# 10_BOOT.net
KiCad netlist of a schematic drawn in Altium Designer
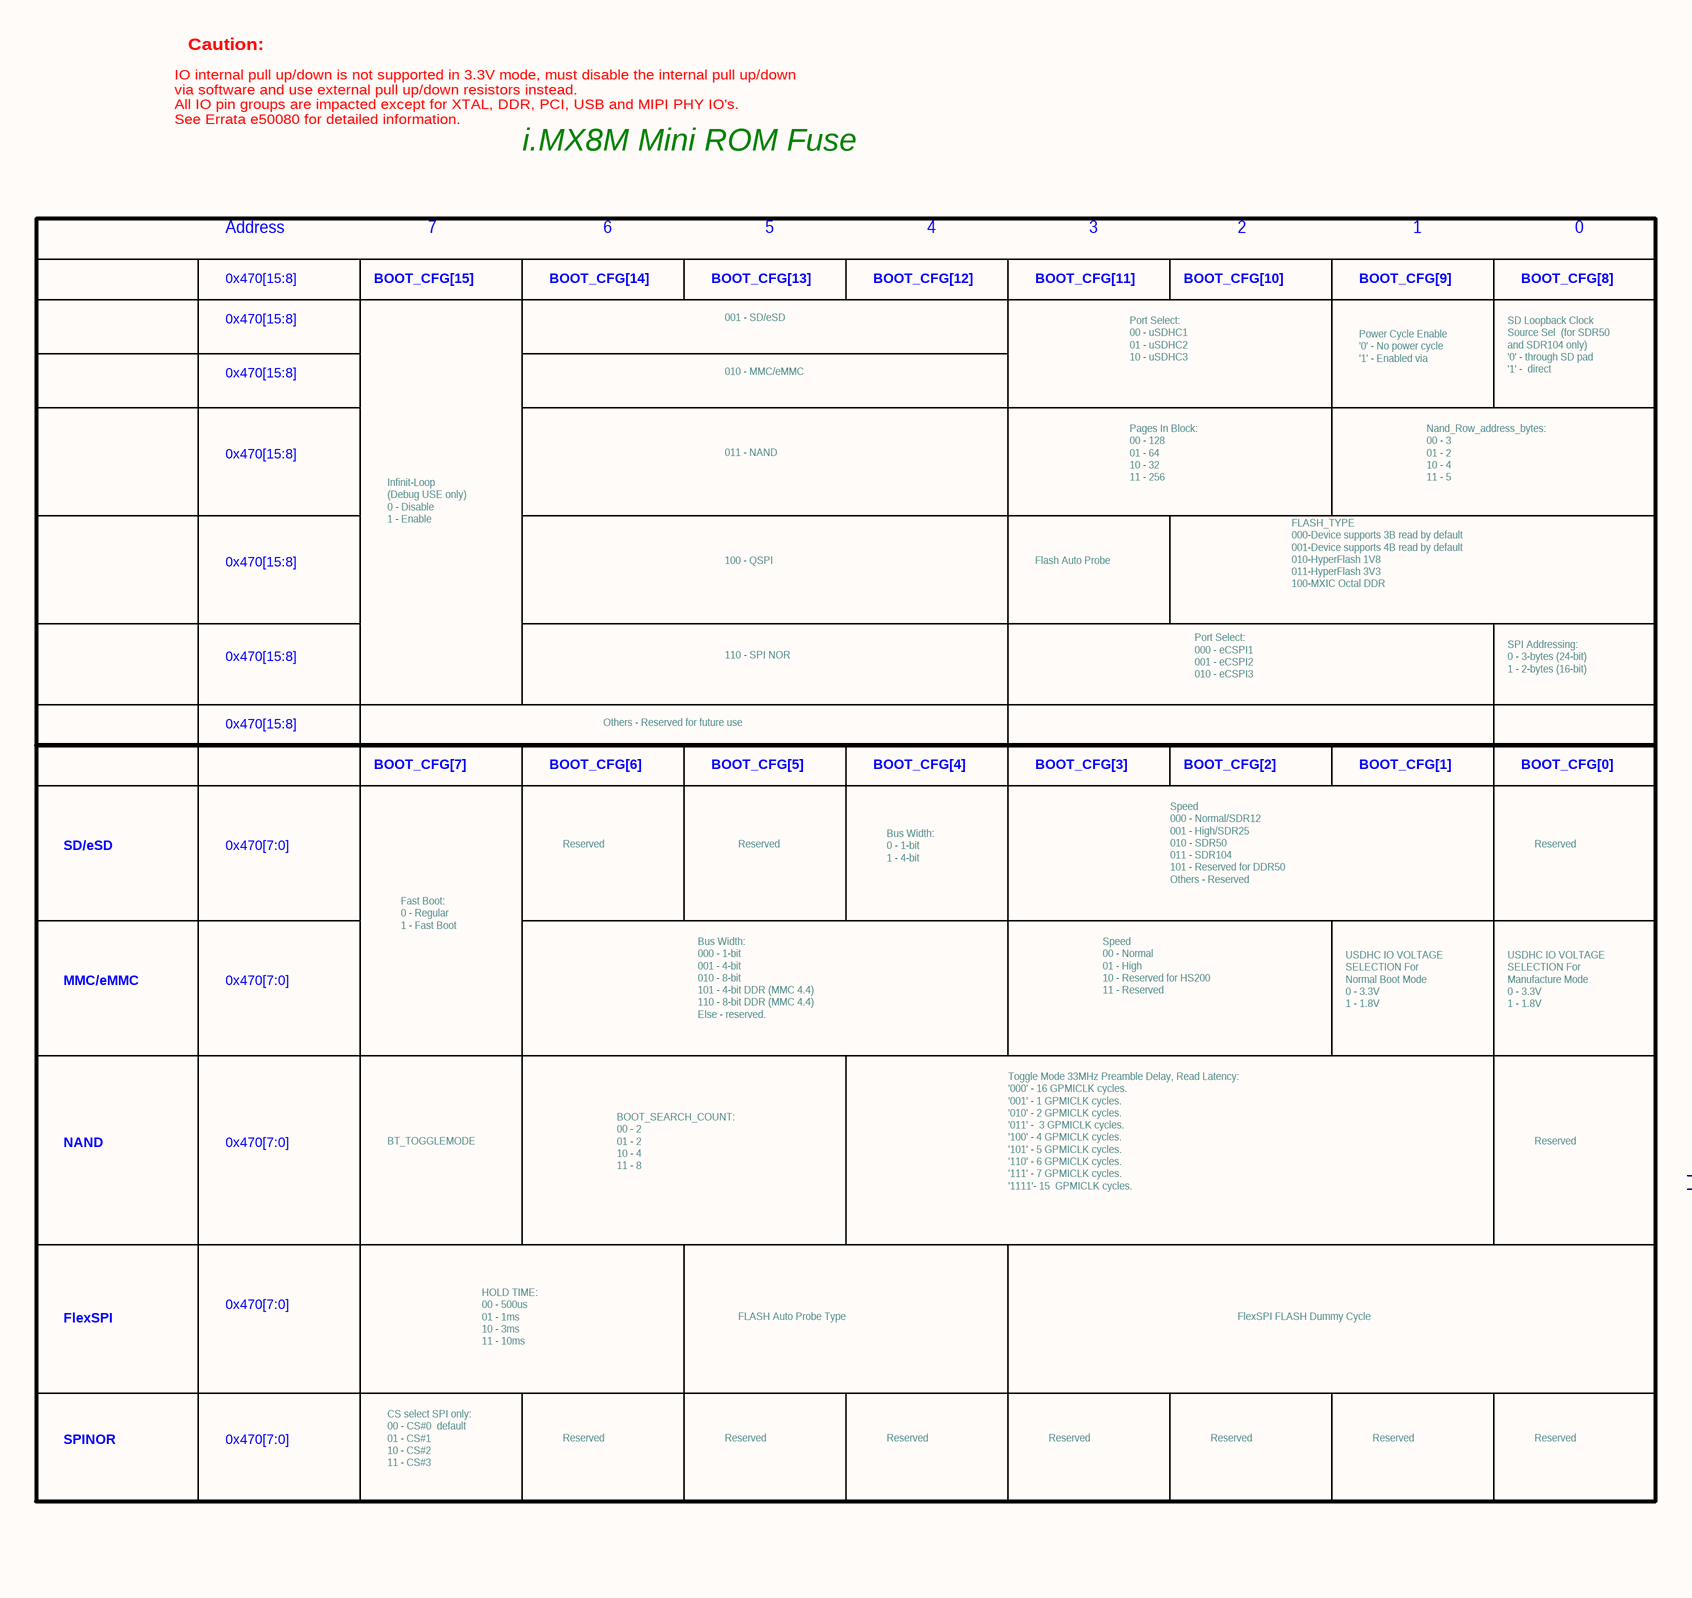
[diagram p0: 10 BOOT.SchDoc, left]
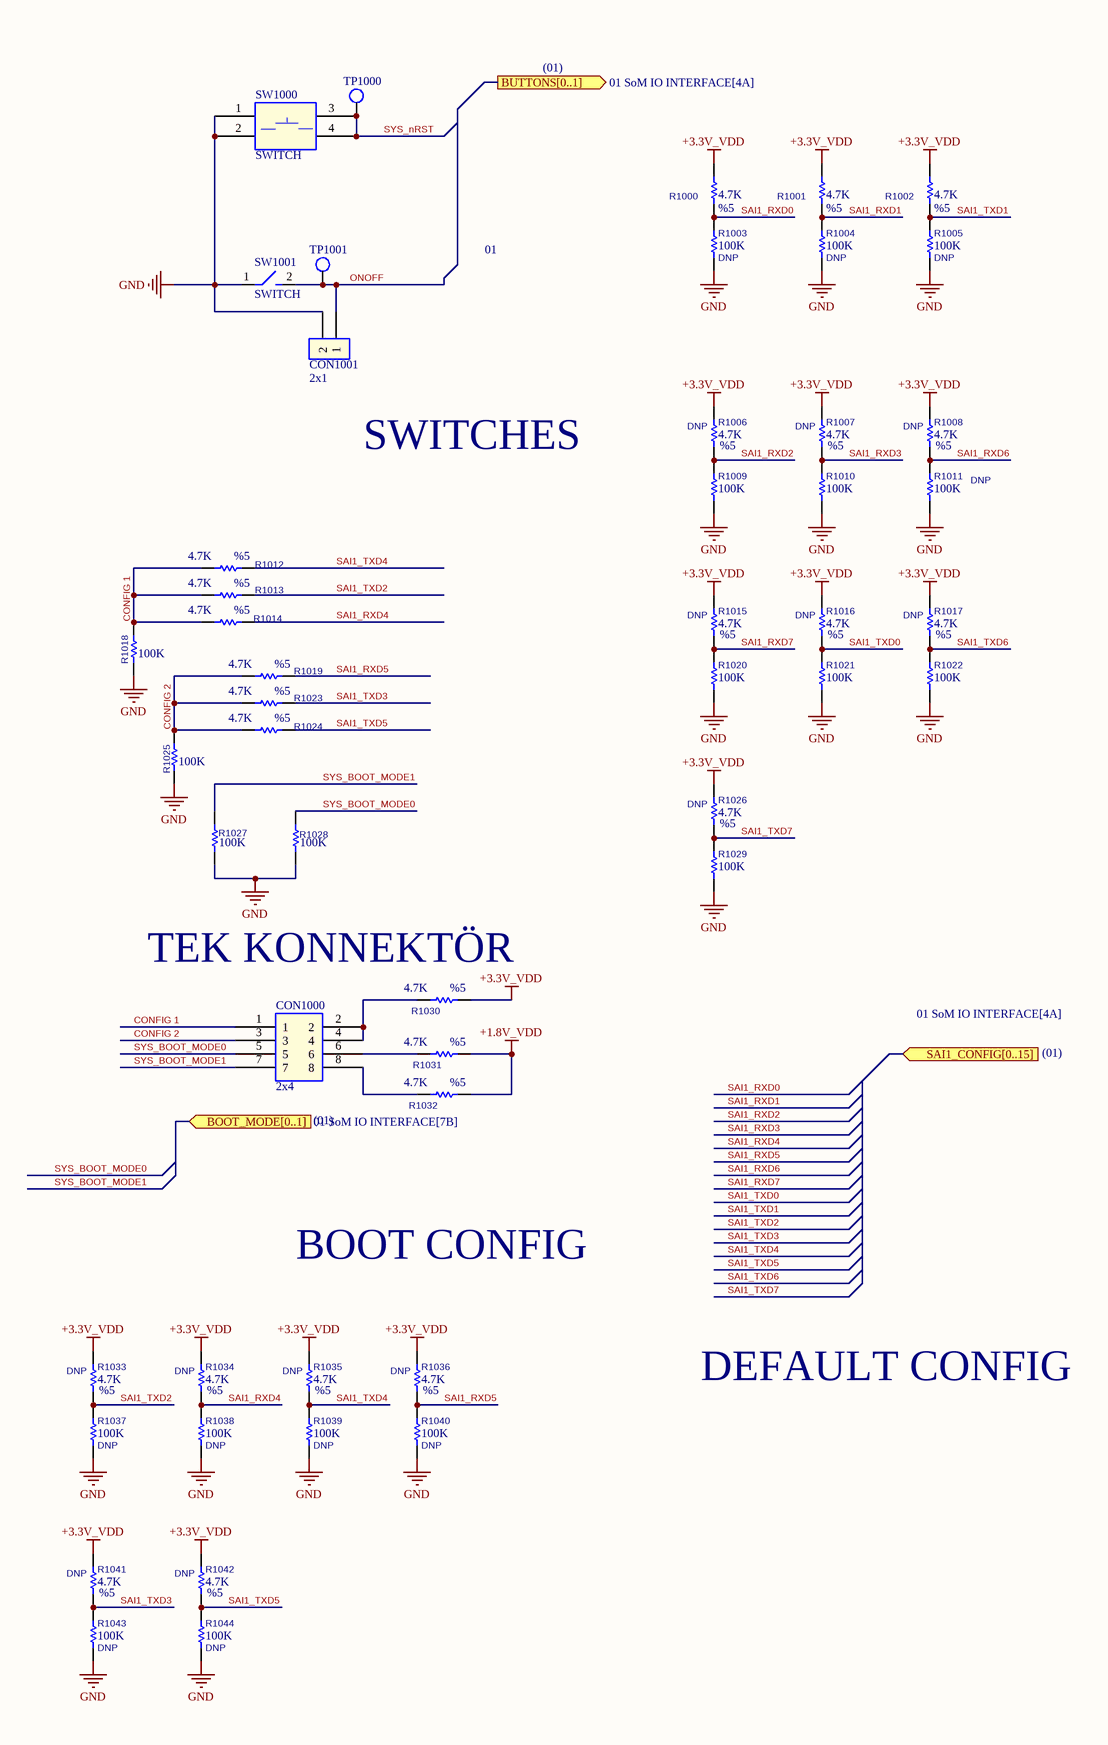
[diagram p1: 10 BOOT.SchDoc, right]

(export (version "E")
  (design (tool "Eeschema 10.0.6"))
  (components
    (comp (ref "CON1000")
      (value "2x4")
      (footprint "HEADER 2.54 X 4x2")
      (description "8 PIN 2.54MM HEADER")
      (fields (field (name "CREATED BY") "*") (field (name "CHECKED BY") "*"))
      (libsource (lib "ARETE_L") (part "CON-8 PIN 2.54MM"))
    )
    (comp (ref "CON1001")
      (value "2x1")
      (footprint "HEADER 1X2 2.54mm")
      (description "2 PIN 2.54 HEADER")
      (fields (field (name "CREATED BY") "*") (field (name "CHECKED BY") "*"))
      (libsource (lib "ARETE_V2_SCH") (part "CON-2 PIN 2.54"))
    )
    (comp (ref "R1000")
      (value "4.7K")
      (footprint "0402_RES")
      (description "RES 4.7K OHM 5% 1/16W 0402")
      (fields
        (field (name "TOLERANCE") "%5")
        (field (name "CREATED BY") "LA")
        (field (name "CHECKED BY") "*")
      )
      (libsource (lib "ARETE_SCH") (part "RES-4.7K"))
    )
    (comp (ref "R1001")
      (value "4.7K")
      (footprint "0402_RES")
      (description "RES 4.7K OHM 5% 1/16W 0402")
      (fields
        (field (name "TOLERANCE") "%5")
        (field (name "CREATED BY") "LA")
        (field (name "CHECKED BY") "*")
      )
      (libsource (lib "ARETE_SCH") (part "RES-4.7K"))
    )
    (comp (ref "R1002")
      (value "4.7K")
      (footprint "0402_RES")
      (description "RES 4.7K OHM 5% 1/16W 0402")
      (fields
        (field (name "TOLERANCE") "%5")
        (field (name "CREATED BY") "LA")
        (field (name "CHECKED BY") "*")
      )
      (libsource (lib "ARETE_SCH") (part "RES-4.7K"))
    )
    (comp (ref "R1003")
      (value "100K")
      (footprint "0402_RES")
      (description "RES 100K OHM 5% 1/16W 0402")
      (fields
        (field (name "ASSY_OPT") "DNP")
        (field (name "TOLERANCE") "%5")
        (field (name "CREATED BY") "LA")
        (field (name "CHECKED BY") "*")
      )
      (libsource (lib "ARETE_SCH") (part "RES-RMCF0402JT100K"))
    )
    (comp (ref "R1004")
      (value "100K")
      (footprint "0402_RES")
      (description "RES 100K OHM 5% 1/16W 0402")
      (fields
        (field (name "ASSY_OPT") "DNP")
        (field (name "TOLERANCE") "%5")
        (field (name "CREATED BY") "LA")
        (field (name "CHECKED BY") "*")
      )
      (libsource (lib "ARETE_SCH") (part "RES-RMCF0402JT100K"))
    )
    (comp (ref "R1005")
      (value "100K")
      (footprint "0402_RES")
      (description "RES 100K OHM 5% 1/16W 0402")
      (fields
        (field (name "ASSY_OPT") "DNP")
        (field (name "TOLERANCE") "%5")
        (field (name "CREATED BY") "LA")
        (field (name "CHECKED BY") "*")
      )
      (libsource (lib "ARETE_SCH") (part "RES-RMCF0402JT100K"))
    )
    (comp (ref "R1006")
      (value "4.7K")
      (footprint "0402_RES")
      (description "RES 4.7K OHM 5% 1/16W 0402")
      (fields
        (field (name "ASSY_OPT") "DNP")
        (field (name "TOLERANCE") "%5")
        (field (name "CREATED BY") "LA")
        (field (name "CHECKED BY") "*")
      )
      (libsource (lib "ARETE_SCH") (part "RES-4.7K"))
    )
    (comp (ref "R1007")
      (value "4.7K")
      (footprint "0402_RES")
      (description "RES 4.7K OHM 5% 1/16W 0402")
      (fields
        (field (name "ASSY_OPT") "DNP")
        (field (name "TOLERANCE") "%5")
        (field (name "CREATED BY") "LA")
        (field (name "CHECKED BY") "*")
      )
      (libsource (lib "ARETE_SCH") (part "RES-4.7K"))
    )
    (comp (ref "R1008")
      (value "4.7K")
      (footprint "0402_RES")
      (description "RES 4.7K OHM 5% 1/16W 0402")
      (fields
        (field (name "ASSY_OPT") "DNP")
        (field (name "TOLERANCE") "%5")
        (field (name "CREATED BY") "LA")
        (field (name "CHECKED BY") "*")
      )
      (libsource (lib "ARETE_SCH") (part "RES-4.7K"))
    )
    (comp (ref "R1009")
      (value "100K")
      (footprint "0402_RES")
      (description "RES 100K OHM 5% 1/16W 0402")
      (fields
        (field (name "TOLERANCE") "%5")
        (field (name "CREATED BY") "LA")
        (field (name "CHECKED BY") "*")
      )
      (libsource (lib "ARETE_SCH") (part "RES-RMCF0402JT100K"))
    )
    (comp (ref "R1010")
      (value "100K")
      (footprint "0402_RES")
      (description "RES 100K OHM 5% 1/16W 0402")
      (fields
        (field (name "TOLERANCE") "%5")
        (field (name "CREATED BY") "LA")
        (field (name "CHECKED BY") "*")
      )
      (libsource (lib "ARETE_SCH") (part "RES-RMCF0402JT100K"))
    )
    (comp (ref "R1011")
      (value "100K")
      (footprint "0402_RES")
      (description "RES 100K OHM 5% 1/16W 0402")
      (fields
        (field (name "ASSY_OPT") "DNP")
        (field (name "TOLERANCE") "%5")
        (field (name "CREATED BY") "LA")
        (field (name "CHECKED BY") "*")
      )
      (libsource (lib "ARETE_SCH") (part "RES-RMCF0402JT100K"))
    )
    (comp (ref "R1012")
      (value "4.7K")
      (footprint "0402_RES")
      (description "RES 4.7K OHM 5% 1/16W 0402")
      (fields
        (field (name "TOLERANCE") "%5")
        (field (name "CREATED BY") "LA")
        (field (name "CHECKED BY") "*")
      )
      (libsource (lib "ARETE_SCH") (part "RES-4.7K"))
    )
    (comp (ref "R1013")
      (value "4.7K")
      (footprint "0402_RES")
      (description "RES 4.7K OHM 5% 1/16W 0402")
      (fields
        (field (name "TOLERANCE") "%5")
        (field (name "CREATED BY") "LA")
        (field (name "CHECKED BY") "*")
      )
      (libsource (lib "ARETE_SCH") (part "RES-4.7K"))
    )
    (comp (ref "R1014")
      (value "4.7K")
      (footprint "0402_RES")
      (description "RES 4.7K OHM 5% 1/16W 0402")
      (fields
        (field (name "TOLERANCE") "%5")
        (field (name "CREATED BY") "LA")
        (field (name "CHECKED BY") "*")
      )
      (libsource (lib "ARETE_SCH") (part "RES-4.7K"))
    )
    (comp (ref "R1015")
      (value "4.7K")
      (footprint "0402_RES")
      (description "RES 4.7K OHM 5% 1/16W 0402")
      (fields
        (field (name "ASSY_OPT") "DNP")
        (field (name "TOLERANCE") "%5")
        (field (name "CREATED BY") "LA")
        (field (name "CHECKED BY") "*")
      )
      (libsource (lib "ARETE_SCH") (part "RES-4.7K"))
    )
    (comp (ref "R1016")
      (value "4.7K")
      (footprint "0402_RES")
      (description "RES 4.7K OHM 5% 1/16W 0402")
      (fields
        (field (name "ASSY_OPT") "DNP")
        (field (name "TOLERANCE") "%5")
        (field (name "CREATED BY") "LA")
        (field (name "CHECKED BY") "*")
      )
      (libsource (lib "ARETE_SCH") (part "RES-4.7K"))
    )
    (comp (ref "R1017")
      (value "4.7K")
      (footprint "0402_RES")
      (description "RES 4.7K OHM 5% 1/16W 0402")
      (fields
        (field (name "ASSY_OPT") "DNP")
        (field (name "TOLERANCE") "%5")
        (field (name "CREATED BY") "LA")
        (field (name "CHECKED BY") "*")
      )
      (libsource (lib "ARETE_SCH") (part "RES-4.7K"))
    )
    (comp (ref "R1018")
      (value "100K")
      (footprint "0402_RES")
      (description "RES 100K OHM 5% 1/16W 0402")
      (fields
        (field (name "TOLERANCE") "%5")
        (field (name "CREATED BY") "LA")
        (field (name "CHECKED BY") "*")
      )
      (libsource (lib "ARETE_SCH") (part "RES-RMCF0402JT100K"))
    )
    (comp (ref "R1019")
      (value "4.7K")
      (footprint "0402_RES")
      (description "RES 4.7K OHM 5% 1/16W 0402")
      (fields
        (field (name "TOLERANCE") "%5")
        (field (name "CREATED BY") "LA")
        (field (name "CHECKED BY") "*")
      )
      (libsource (lib "ARETE_SCH") (part "RES-4.7K"))
    )
    (comp (ref "R1020")
      (value "100K")
      (footprint "0402_RES")
      (description "RES 100K OHM 5% 1/16W 0402")
      (fields
        (field (name "TOLERANCE") "%5")
        (field (name "CREATED BY") "LA")
        (field (name "CHECKED BY") "*")
      )
      (libsource (lib "ARETE_SCH") (part "RES-RMCF0402JT100K"))
    )
    (comp (ref "R1021")
      (value "100K")
      (footprint "0402_RES")
      (description "RES 100K OHM 5% 1/16W 0402")
      (fields
        (field (name "TOLERANCE") "%5")
        (field (name "CREATED BY") "LA")
        (field (name "CHECKED BY") "*")
      )
      (libsource (lib "ARETE_SCH") (part "RES-RMCF0402JT100K"))
    )
    (comp (ref "R1022")
      (value "100K")
      (footprint "0402_RES")
      (description "RES 100K OHM 5% 1/16W 0402")
      (fields
        (field (name "TOLERANCE") "%5")
        (field (name "CREATED BY") "LA")
        (field (name "CHECKED BY") "*")
      )
      (libsource (lib "ARETE_SCH") (part "RES-RMCF0402JT100K"))
    )
    (comp (ref "R1023")
      (value "4.7K")
      (footprint "0402_RES")
      (description "RES 4.7K OHM 5% 1/16W 0402")
      (fields
        (field (name "TOLERANCE") "%5")
        (field (name "CREATED BY") "LA")
        (field (name "CHECKED BY") "*")
      )
      (libsource (lib "ARETE_SCH") (part "RES-4.7K"))
    )
    (comp (ref "R1024")
      (value "4.7K")
      (footprint "0402_RES")
      (description "RES 4.7K OHM 5% 1/16W 0402")
      (fields
        (field (name "TOLERANCE") "%5")
        (field (name "CREATED BY") "LA")
        (field (name "CHECKED BY") "*")
      )
      (libsource (lib "ARETE_SCH") (part "RES-4.7K"))
    )
    (comp (ref "R1025")
      (value "100K")
      (footprint "0402_RES")
      (description "RES 100K OHM 5% 1/16W 0402")
      (fields
        (field (name "TOLERANCE") "%5")
        (field (name "CREATED BY") "LA")
        (field (name "CHECKED BY") "*")
      )
      (libsource (lib "ARETE_SCH") (part "RES-RMCF0402JT100K"))
    )
    (comp (ref "R1026")
      (value "4.7K")
      (footprint "0402_RES")
      (description "RES 4.7K OHM 5% 1/16W 0402")
      (fields
        (field (name "ASSY_OPT") "DNP")
        (field (name "TOLERANCE") "%5")
        (field (name "CREATED BY") "LA")
        (field (name "CHECKED BY") "*")
      )
      (libsource (lib "ARETE_SCH") (part "RES-4.7K"))
    )
    (comp (ref "R1027")
      (value "100K")
      (footprint "0402_RES")
      (description "RES 100K OHM 5% 1/16W 0402")
      (fields
        (field (name "TOLERANCE") "%5")
        (field (name "CREATED BY") "LA")
        (field (name "CHECKED BY") "*")
      )
      (libsource (lib "ARETE_SCH") (part "RES-RMCF0402JT100K"))
    )
    (comp (ref "R1028")
      (value "100K")
      (footprint "0402_RES")
      (description "RES 100K OHM 5% 1/16W 0402")
      (fields
        (field (name "TOLERANCE") "%5")
        (field (name "CREATED BY") "LA")
        (field (name "CHECKED BY") "*")
      )
      (libsource (lib "ARETE_SCH") (part "RES-RMCF0402JT100K"))
    )
    (comp (ref "R1029")
      (value "100K")
      (footprint "0402_RES")
      (description "RES 100K OHM 5% 1/16W 0402")
      (fields
        (field (name "TOLERANCE") "%5")
        (field (name "CREATED BY") "LA")
        (field (name "CHECKED BY") "*")
      )
      (libsource (lib "ARETE_SCH") (part "RES-RMCF0402JT100K"))
    )
    (comp (ref "R1030")
      (value "4.7K")
      (footprint "0402_RES")
      (description "RES 4.7K OHM 5% 1/16W 0402")
      (fields
        (field (name "TOLERANCE") "%5")
        (field (name "CREATED BY") "LA")
        (field (name "CHECKED BY") "*")
      )
      (libsource (lib "ARETE_SCH") (part "RES-4.7K"))
    )
    (comp (ref "R1031")
      (value "4.7K")
      (footprint "0402_RES")
      (description "RES 4.7K OHM 5% 1/16W 0402")
      (fields
        (field (name "TOLERANCE") "%5")
        (field (name "CREATED BY") "LA")
        (field (name "CHECKED BY") "*")
      )
      (libsource (lib "ARETE_SCH") (part "RES-4.7K"))
    )
    (comp (ref "R1032")
      (value "4.7K")
      (footprint "0402_RES")
      (description "RES 4.7K OHM 5% 1/16W 0402")
      (fields
        (field (name "TOLERANCE") "%5")
        (field (name "CREATED BY") "LA")
        (field (name "CHECKED BY") "*")
      )
      (libsource (lib "ARETE_SCH") (part "RES-4.7K"))
    )
    (comp (ref "R1033")
      (value "4.7K")
      (footprint "0402_RES")
      (description "RES 4.7K OHM 5% 1/16W 0402")
      (fields
        (field (name "ASSY_OPT") "DNP")
        (field (name "TOLERANCE") "%5")
        (field (name "CREATED BY") "LA")
        (field (name "CHECKED BY") "*")
      )
      (libsource (lib "ARETE_SCH") (part "RES-4.7K"))
    )
    (comp (ref "R1034")
      (value "4.7K")
      (footprint "0402_RES")
      (description "RES 4.7K OHM 5% 1/16W 0402")
      (fields
        (field (name "ASSY_OPT") "DNP")
        (field (name "TOLERANCE") "%5")
        (field (name "CREATED BY") "LA")
        (field (name "CHECKED BY") "*")
      )
      (libsource (lib "ARETE_SCH") (part "RES-4.7K"))
    )
    (comp (ref "R1035")
      (value "4.7K")
      (footprint "0402_RES")
      (description "RES 4.7K OHM 5% 1/16W 0402")
      (fields
        (field (name "ASSY_OPT") "DNP")
        (field (name "TOLERANCE") "%5")
        (field (name "CREATED BY") "LA")
        (field (name "CHECKED BY") "*")
      )
      (libsource (lib "ARETE_SCH") (part "RES-4.7K"))
    )
    (comp (ref "R1036")
      (value "4.7K")
      (footprint "0402_RES")
      (description "RES 4.7K OHM 5% 1/16W 0402")
      (fields
        (field (name "ASSY_OPT") "DNP")
        (field (name "TOLERANCE") "%5")
        (field (name "CREATED BY") "LA")
        (field (name "CHECKED BY") "*")
      )
      (libsource (lib "ARETE_SCH") (part "RES-4.7K"))
    )
    (comp (ref "R1037")
      (value "100K")
      (footprint "0402_RES")
      (description "RES 100K OHM 5% 1/16W 0402")
      (fields
        (field (name "ASSY_OPT") "DNP")
        (field (name "TOLERANCE") "%5")
        (field (name "CREATED BY") "LA")
        (field (name "CHECKED BY") "*")
      )
      (libsource (lib "ARETE_SCH") (part "RES-RMCF0402JT100K"))
    )
    (comp (ref "R1038")
      (value "100K")
      (footprint "0402_RES")
      (description "RES 100K OHM 5% 1/16W 0402")
      (fields
        (field (name "ASSY_OPT") "DNP")
        (field (name "TOLERANCE") "%5")
        (field (name "CREATED BY") "LA")
        (field (name "CHECKED BY") "*")
      )
      (libsource (lib "ARETE_SCH") (part "RES-RMCF0402JT100K"))
    )
    (comp (ref "R1039")
      (value "100K")
      (footprint "0402_RES")
      (description "RES 100K OHM 5% 1/16W 0402")
      (fields
        (field (name "ASSY_OPT") "DNP")
        (field (name "TOLERANCE") "%5")
        (field (name "CREATED BY") "LA")
        (field (name "CHECKED BY") "*")
      )
      (libsource (lib "ARETE_SCH") (part "RES-RMCF0402JT100K"))
    )
    (comp (ref "R1040")
      (value "100K")
      (footprint "0402_RES")
      (description "RES 100K OHM 5% 1/16W 0402")
      (fields
        (field (name "ASSY_OPT") "DNP")
        (field (name "TOLERANCE") "%5")
        (field (name "CREATED BY") "LA")
        (field (name "CHECKED BY") "*")
      )
      (libsource (lib "ARETE_SCH") (part "RES-RMCF0402JT100K"))
    )
    (comp (ref "R1041")
      (value "4.7K")
      (footprint "0402_RES")
      (description "RES 4.7K OHM 5% 1/16W 0402")
      (fields
        (field (name "ASSY_OPT") "DNP")
        (field (name "TOLERANCE") "%5")
        (field (name "CREATED BY") "LA")
        (field (name "CHECKED BY") "*")
      )
      (libsource (lib "ARETE_SCH") (part "RES-4.7K"))
    )
    (comp (ref "R1042")
      (value "4.7K")
      (footprint "0402_RES")
      (description "RES 4.7K OHM 5% 1/16W 0402")
      (fields
        (field (name "ASSY_OPT") "DNP")
        (field (name "TOLERANCE") "%5")
        (field (name "CREATED BY") "LA")
        (field (name "CHECKED BY") "*")
      )
      (libsource (lib "ARETE_SCH") (part "RES-4.7K"))
    )
    (comp (ref "R1043")
      (value "100K")
      (footprint "0402_RES")
      (description "RES 100K OHM 5% 1/16W 0402")
      (fields
        (field (name "ASSY_OPT") "DNP")
        (field (name "TOLERANCE") "%5")
        (field (name "CREATED BY") "LA")
        (field (name "CHECKED BY") "*")
      )
      (libsource (lib "ARETE_SCH") (part "RES-RMCF0402JT100K"))
    )
    (comp (ref "R1044")
      (value "100K")
      (footprint "0402_RES")
      (description "RES 100K OHM 5% 1/16W 0402")
      (fields
        (field (name "ASSY_OPT") "DNP")
        (field (name "TOLERANCE") "%5")
        (field (name "CREATED BY") "LA")
        (field (name "CHECKED BY") "*")
      )
      (libsource (lib "ARETE_SCH") (part "RES-RMCF0402JT100K"))
    )
    (comp (ref "SW1000")
      (value "SWITCH")
      (footprint "BUTTON 6x6")
      (description "SWITCH TACT 6x6MM 8.5MM 160gf SMD")
      (fields (field (name "CREATED BY") "LA") (field (name "CHECKED BY") "*"))
      (libsource (lib "ARETE_SCH") (part "SW-DS1042-03-1-9-KKR-160-10"))
    )
    (comp (ref "SW1001")
      (value "SWITCH")
      (footprint "3.00mm x 2.00mm SWITCH")
      (description "SWITCH TACTILE, SPST-NO, 0.02A 1")
      (fields (field (name "CREATED BY") "EE") (field (name "CHECKED BY") "*"))
      (libsource (lib "ARETE_V2_SCH") (part "SW-STO-060A16AB"))
    )
    (comp (ref "TP1000")
      (value "TEST POINT 15")
      (footprint "testpoint_15")
      (libsource (lib "X98_CARRIER_V1R2") (part "TEST POINT 15"))
    )
    (comp (ref "TP1001")
      (value "TEST POINT 15")
      (footprint "testpoint_15")
      (libsource (lib "X98_CARRIER_V1R2") (part "TEST POINT 15"))
    )
  )
  (nets
    (net (code "21") (name "+1.8V_VDD") (class "Default")
      (node (ref "R1031") (pin "1") (pinfunction "1_1") (pintype "passive"))
      (node (ref "R1032") (pin "1") (pinfunction "1_1") (pintype "passive"))
    )
    (net (code "22") (name "+3.3V_VDD") (class "Default")
      (node (ref "R1000") (pin "2") (pinfunction "2_2") (pintype "passive"))
      (node (ref "R1001") (pin "2") (pinfunction "2_2") (pintype "passive"))
      (node (ref "R1002") (pin "2") (pinfunction "2_2") (pintype "passive"))
      (node (ref "R1006") (pin "2") (pinfunction "2_2") (pintype "passive"))
      (node (ref "R1007") (pin "2") (pinfunction "2_2") (pintype "passive"))
      (node (ref "R1008") (pin "2") (pinfunction "2_2") (pintype "passive"))
      (node (ref "R1015") (pin "2") (pinfunction "2_2") (pintype "passive"))
      (node (ref "R1016") (pin "2") (pinfunction "2_2") (pintype "passive"))
      (node (ref "R1017") (pin "2") (pinfunction "2_2") (pintype "passive"))
      (node (ref "R1026") (pin "2") (pinfunction "2_2") (pintype "passive"))
      (node (ref "R1030") (pin "1") (pinfunction "1_1") (pintype "passive"))
      (node (ref "R1033") (pin "2") (pinfunction "2_2") (pintype "passive"))
      (node (ref "R1034") (pin "2") (pinfunction "2_2") (pintype "passive"))
      (node (ref "R1035") (pin "2") (pinfunction "2_2") (pintype "passive"))
      (node (ref "R1036") (pin "2") (pinfunction "2_2") (pintype "passive"))
      (node (ref "R1041") (pin "2") (pinfunction "2_2") (pintype "passive"))
      (node (ref "R1042") (pin "2") (pinfunction "2_2") (pintype "passive"))
    )
    (net (code "25") (name "/CONFIG 1") (class "Default")
      (node (ref "CON1000") (pin "1") (pinfunction "1_1") (pintype "passive"))
      (node (ref "R1012") (pin "2") (pinfunction "2_2") (pintype "passive"))
      (node (ref "R1013") (pin "2") (pinfunction "2_2") (pintype "passive"))
      (node (ref "R1014") (pin "2") (pinfunction "2_2") (pintype "passive"))
      (node (ref "R1018") (pin "2") (pinfunction "2_2") (pintype "passive"))
    )
    (net (code "26") (name "/CONFIG 2") (class "Default")
      (node (ref "CON1000") (pin "3") (pinfunction "3_3") (pintype "passive"))
      (node (ref "R1019") (pin "2") (pinfunction "2_2") (pintype "passive"))
      (node (ref "R1023") (pin "2") (pinfunction "2_2") (pintype "passive"))
      (node (ref "R1024") (pin "2") (pinfunction "2_2") (pintype "passive"))
      (node (ref "R1025") (pin "2") (pinfunction "2_2") (pintype "passive"))
    )
    (net (code "27") (name "/ONOFF") (class "Default")
      (node (ref "CON1001") (pin "1") (pinfunction "1_1") (pintype "passive"))
      (node (ref "SW1001") (pin "2") (pinfunction "2_2") (pintype "passive"))
      (node (ref "TP1001") (pin "1") (pinfunction "1_1") (pintype "passive"))
    )
    (net (code "29") (name "/SAI1_RXD0") (class "Default")
      (node (ref "R1000") (pin "1") (pinfunction "1_1") (pintype "passive"))
      (node (ref "R1003") (pin "2") (pinfunction "2_2") (pintype "passive"))
    )
    (net (code "30") (name "/SAI1_RXD1") (class "Default")
      (node (ref "R1001") (pin "1") (pinfunction "1_1") (pintype "passive"))
      (node (ref "R1004") (pin "2") (pinfunction "2_2") (pintype "passive"))
    )
    (net (code "31") (name "/SAI1_RXD2") (class "Default")
      (node (ref "R1006") (pin "1") (pinfunction "1_1") (pintype "passive"))
      (node (ref "R1009") (pin "2") (pinfunction "2_2") (pintype "passive"))
    )
    (net (code "32") (name "/SAI1_RXD3") (class "Default")
      (node (ref "R1007") (pin "1") (pinfunction "1_1") (pintype "passive"))
      (node (ref "R1010") (pin "2") (pinfunction "2_2") (pintype "passive"))
    )
    (net (code "33") (name "/SAI1_RXD4") (class "Default")
      (node (ref "R1014") (pin "1") (pinfunction "1_1") (pintype "passive"))
      (node (ref "R1034") (pin "1") (pinfunction "1_1") (pintype "passive"))
      (node (ref "R1038") (pin "2") (pinfunction "2_2") (pintype "passive"))
    )
    (net (code "34") (name "/SAI1_RXD5") (class "Default")
      (node (ref "R1019") (pin "1") (pinfunction "1_1") (pintype "passive"))
      (node (ref "R1036") (pin "1") (pinfunction "1_1") (pintype "passive"))
      (node (ref "R1040") (pin "2") (pinfunction "2_2") (pintype "passive"))
    )
    (net (code "35") (name "/SAI1_RXD6") (class "Default")
      (node (ref "R1008") (pin "1") (pinfunction "1_1") (pintype "passive"))
      (node (ref "R1011") (pin "2") (pinfunction "2_2") (pintype "passive"))
    )
    (net (code "36") (name "/SAI1_RXD7") (class "Default")
      (node (ref "R1015") (pin "1") (pinfunction "1_1") (pintype "passive"))
      (node (ref "R1020") (pin "2") (pinfunction "2_2") (pintype "passive"))
    )
    (net (code "37") (name "/SAI1_TXD0") (class "Default")
      (node (ref "R1016") (pin "1") (pinfunction "1_1") (pintype "passive"))
      (node (ref "R1021") (pin "2") (pinfunction "2_2") (pintype "passive"))
    )
    (net (code "38") (name "/SAI1_TXD1") (class "Default")
      (node (ref "R1002") (pin "1") (pinfunction "1_1") (pintype "passive"))
      (node (ref "R1005") (pin "2") (pinfunction "2_2") (pintype "passive"))
    )
    (net (code "39") (name "/SAI1_TXD2") (class "Default")
      (node (ref "R1013") (pin "1") (pinfunction "1_1") (pintype "passive"))
      (node (ref "R1033") (pin "1") (pinfunction "1_1") (pintype "passive"))
      (node (ref "R1037") (pin "2") (pinfunction "2_2") (pintype "passive"))
    )
    (net (code "40") (name "/SAI1_TXD3") (class "Default")
      (node (ref "R1023") (pin "1") (pinfunction "1_1") (pintype "passive"))
      (node (ref "R1041") (pin "1") (pinfunction "1_1") (pintype "passive"))
      (node (ref "R1043") (pin "2") (pinfunction "2_2") (pintype "passive"))
    )
    (net (code "41") (name "/SAI1_TXD4") (class "Default")
      (node (ref "R1012") (pin "1") (pinfunction "1_1") (pintype "passive"))
      (node (ref "R1035") (pin "1") (pinfunction "1_1") (pintype "passive"))
      (node (ref "R1039") (pin "2") (pinfunction "2_2") (pintype "passive"))
    )
    (net (code "42") (name "/SAI1_TXD5") (class "Default")
      (node (ref "R1024") (pin "1") (pinfunction "1_1") (pintype "passive"))
      (node (ref "R1042") (pin "1") (pinfunction "1_1") (pintype "passive"))
      (node (ref "R1044") (pin "2") (pinfunction "2_2") (pintype "passive"))
    )
    (net (code "43") (name "/SAI1_TXD6") (class "Default")
      (node (ref "R1017") (pin "1") (pinfunction "1_1") (pintype "passive"))
      (node (ref "R1022") (pin "2") (pinfunction "2_2") (pintype "passive"))
    )
    (net (code "44") (name "/SAI1_TXD7") (class "Default")
      (node (ref "R1026") (pin "1") (pinfunction "1_1") (pintype "passive"))
      (node (ref "R1029") (pin "2") (pinfunction "2_2") (pintype "passive"))
    )
    (net (code "45") (name "/SYS_BOOT_MODE0") (class "Default")
      (node (ref "CON1000") (pin "5") (pinfunction "5_5") (pintype "passive"))
      (node (ref "R1028") (pin "2") (pinfunction "2_2") (pintype "passive"))
    )
    (net (code "46") (name "/SYS_BOOT_MODE1") (class "Default")
      (node (ref "CON1000") (pin "7") (pinfunction "7_7") (pintype "passive"))
      (node (ref "R1027") (pin "2") (pinfunction "2_2") (pintype "passive"))
    )
    (net (code "47") (name "/SYS_nRST") (class "Default")
      (node (ref "SW1000") (pin "3") (pinfunction "3_3") (pintype "passive"))
      (node (ref "SW1000") (pin "4") (pinfunction "4_4") (pintype "passive"))
      (node (ref "TP1000") (pin "1") (pinfunction "1_1") (pintype "passive"))
    )
    (net (code "48") (name "GND") (class "Default")
      (node (ref "CON1001") (pin "2") (pinfunction "2_2") (pintype "passive"))
      (node (ref "R1003") (pin "1") (pinfunction "1_1") (pintype "passive"))
      (node (ref "R1004") (pin "1") (pinfunction "1_1") (pintype "passive"))
      (node (ref "R1005") (pin "1") (pinfunction "1_1") (pintype "passive"))
      (node (ref "R1009") (pin "1") (pinfunction "1_1") (pintype "passive"))
      (node (ref "R1010") (pin "1") (pinfunction "1_1") (pintype "passive"))
      (node (ref "R1011") (pin "1") (pinfunction "1_1") (pintype "passive"))
      (node (ref "R1018") (pin "1") (pinfunction "1_1") (pintype "passive"))
      (node (ref "R1020") (pin "1") (pinfunction "1_1") (pintype "passive"))
      (node (ref "R1021") (pin "1") (pinfunction "1_1") (pintype "passive"))
      (node (ref "R1022") (pin "1") (pinfunction "1_1") (pintype "passive"))
      (node (ref "R1025") (pin "1") (pinfunction "1_1") (pintype "passive"))
      (node (ref "R1027") (pin "1") (pinfunction "1_1") (pintype "passive"))
      (node (ref "R1028") (pin "1") (pinfunction "1_1") (pintype "passive"))
      (node (ref "R1029") (pin "1") (pinfunction "1_1") (pintype "passive"))
      (node (ref "R1037") (pin "1") (pinfunction "1_1") (pintype "passive"))
      (node (ref "R1038") (pin "1") (pinfunction "1_1") (pintype "passive"))
      (node (ref "R1039") (pin "1") (pinfunction "1_1") (pintype "passive"))
      (node (ref "R1040") (pin "1") (pinfunction "1_1") (pintype "passive"))
      (node (ref "R1043") (pin "1") (pinfunction "1_1") (pintype "passive"))
      (node (ref "R1044") (pin "1") (pinfunction "1_1") (pintype "passive"))
      (node (ref "SW1000") (pin "1") (pinfunction "1_1") (pintype "passive"))
      (node (ref "SW1000") (pin "2") (pinfunction "2_2") (pintype "passive"))
      (node (ref "SW1001") (pin "1") (pinfunction "1_1") (pintype "passive"))
    )
    (net (code "49") (name "Net-(CON1000-Pad2)") (class "Default")
      (node (ref "CON1000") (pin "2") (pinfunction "2_2") (pintype "passive"))
      (node (ref "CON1000") (pin "4") (pinfunction "4_4") (pintype "passive"))
      (node (ref "R1030") (pin "2") (pinfunction "2_2") (pintype "passive"))
    )
    (net (code "50") (name "Net-(CON1000-Pad6)") (class "Default")
      (node (ref "CON1000") (pin "6") (pinfunction "6_6") (pintype "passive"))
      (node (ref "R1031") (pin "2") (pinfunction "2_2") (pintype "passive"))
    )
    (net (code "51") (name "Net-(CON1000-Pad8)") (class "Default")
      (node (ref "CON1000") (pin "8") (pinfunction "8_8") (pintype "passive"))
      (node (ref "R1032") (pin "2") (pinfunction "2_2") (pintype "passive"))
    )
  )
)
